# Buck_Converter.net
KiCad netlist of a schematic drawn in Altium Designer
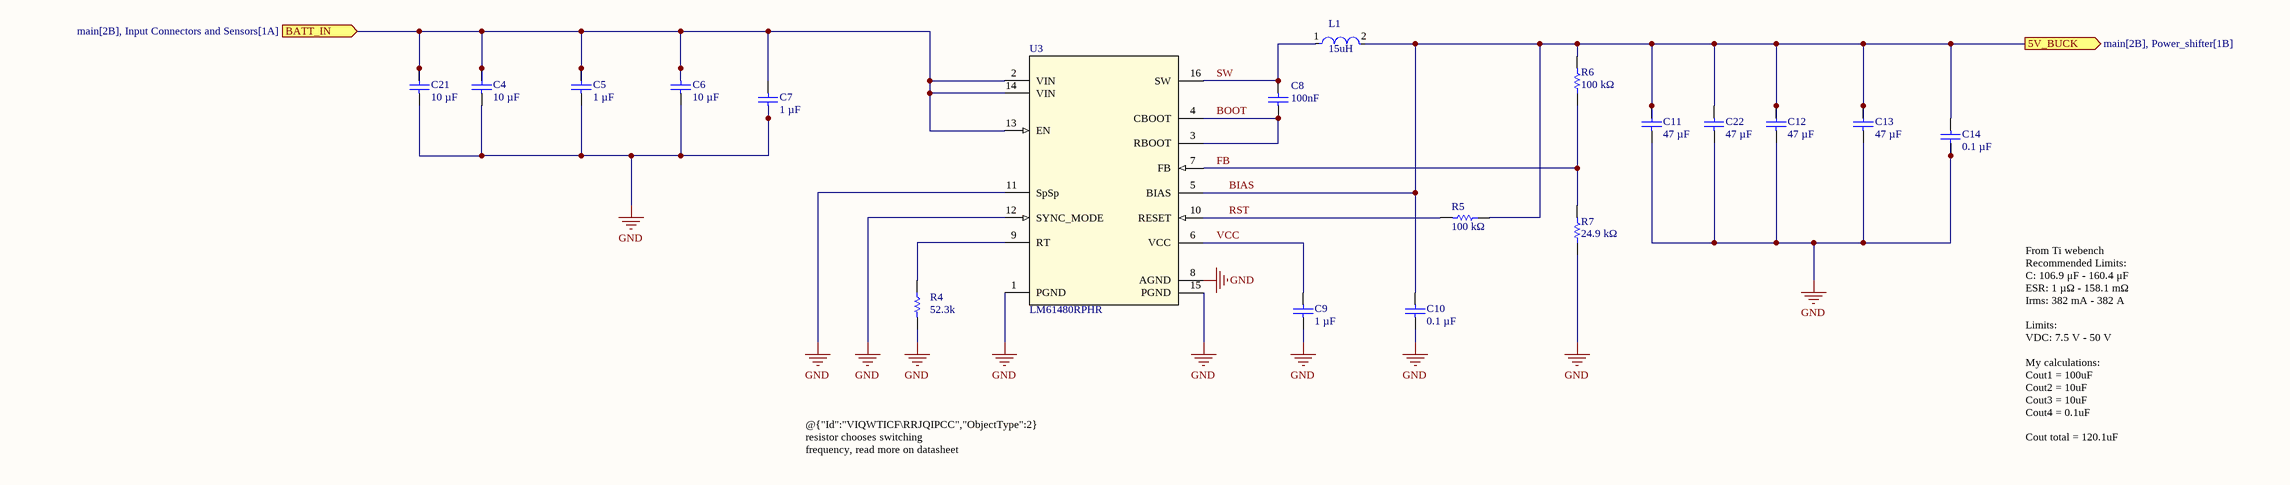
[diagram p0: Buck Converter.SchDoc]

(export (version "E")
  (design (tool "Eeschema 10.0.6"))
  (components
    (comp (ref "C4")
      (value "10 µF")
      (footprint "1210_CAPC3225L")
      (description "Capacitor (Semiconductor SIM Model)")
      (fields (field (name "PUBLISHER") "Altium Limited"))
      (libsource (lib "MiscDev 3") (part "Cap Semi"))
    )
    (comp (ref "C5")
      (value "1 µF")
      (footprint "0603_CAPC1608L")
      (description "Capacitor (Semiconductor SIM Model)")
      (fields (field (name "PUBLISHER") "Altium Limited"))
      (libsource (lib "MiscDev 3") (part "Cap Semi"))
    )
    (comp (ref "C6")
      (value "10 µF")
      (footprint "1210_CAPC3225L")
      (description "Capacitor (Semiconductor SIM Model)")
      (fields (field (name "PUBLISHER") "Altium Limited"))
      (libsource (lib "MiscDev 3") (part "Cap Semi"))
    )
    (comp (ref "C7")
      (value "1 µF")
      (footprint "0603_CAPC1608L")
      (description "Capacitor (Semiconductor SIM Model)")
      (fields (field (name "PUBLISHER") "Altium Limited"))
      (libsource (lib "MiscDev 3") (part "Cap Semi"))
    )
    (comp (ref "C8")
      (value "GRM155R71A104KA01D")
      (footprint "CAPC1005X55X25LL05T10")
      (description "Chip Capacitor, 0.1 uF, +/- 10%, 10 V, -55 to 125 degC, 0402 (1005 Metric), RoHS, Tape and Reel")
      (fields (field (name "CAPACITANCE") "100nF") (field (name "MANUFACTURER") "Murata"))
      (libsource (lib "Altium Content Vault") (part "CAP-NP-2"))
    )
    (comp (ref "C9")
      (value "1 µF")
      (footprint "0603_CAPC1608L")
      (description "Capacitor (Semiconductor SIM Model)")
      (fields (field (name "PUBLISHER") "Altium Limited"))
      (libsource (lib "MiscDev 3") (part "Cap Semi"))
    )
    (comp (ref "C10")
      (value "0.1 µF")
      (footprint "0402_CAPC1005L")
      (description "Capacitor (Semiconductor SIM Model)")
      (fields (field (name "PUBLISHER") "Altium Limited"))
      (libsource (lib "MiscDev 3") (part "Cap Semi"))
    )
    (comp (ref "C11")
      (value "47 µF")
      (footprint "1210_CAPC3225L")
      (description "Capacitor (Semiconductor SIM Model)")
      (fields (field (name "PUBLISHER") "Altium Limited"))
      (libsource (lib "MiscDev 3") (part "Cap Semi"))
    )
    (comp (ref "C12")
      (value "47 µF")
      (footprint "1210_CAPC3225L")
      (description "Capacitor (Semiconductor SIM Model)")
      (fields (field (name "PUBLISHER") "Altium Limited"))
      (libsource (lib "MiscDev 3") (part "Cap Semi"))
    )
    (comp (ref "C13")
      (value "47 µF")
      (footprint "1210_CAPC3225L")
      (description "Capacitor (Semiconductor SIM Model)")
      (fields (field (name "PUBLISHER") "Altium Limited"))
      (libsource (lib "MiscDev 3") (part "Cap Semi"))
    )
    (comp (ref "C14")
      (value "0.1 µF")
      (footprint "0402_CAPC1005L")
      (description "Capacitor (Semiconductor SIM Model)")
      (fields (field (name "PUBLISHER") "Altium Limited"))
      (libsource (lib "MiscDev 3") (part "Cap Semi"))
    )
    (comp (ref "C21")
      (value "10 µF")
      (footprint "1210_CAPC3225L")
      (description "Capacitor (Semiconductor SIM Model)")
      (fields (field (name "PUBLISHER") "Altium Limited"))
      (libsource (lib "MiscDev 3") (part "Cap Semi"))
    )
    (comp (ref "C22")
      (value "47 µF")
      (footprint "1210_CAPC3225L")
      (description "Capacitor (Semiconductor SIM Model)")
      (fields (field (name "PUBLISHER") "Altium Limited"))
      (libsource (lib "MiscDev 3") (part "Cap Semi"))
    )
    (comp (ref "L1")
      (value "SRR1260-150M")
      (footprint "FP-SRR1260-MFG")
      (description "FIXED IND 15UH 5A 27 MOHM SMD")
      (fields (field (name "INDUCTANCE") "15uH") (field (name "TOLERANCE") "20%"))
      (libsource (lib "Altium Content Vault") (part "725321dda6339637d4d059423bc1c3c"))
    )
    (comp (ref "R4")
      (value "CRCW040252K3FKED")
      (footprint "RESC1005X40X25LL05T05")
      (fields (field (name "MANUFACTURER") "Vishay Dale") (field (name "RESISTANCE") "52.3k"))
      (libsource (lib "Altium Content Vault") (part "RES"))
    )
    (comp (ref "R5")
      (value "100 kΩ")
      (footprint "0603_RESC1608L")
      (description "Semiconductor Resistor")
      (fields (field (name "Comment") "Res Semi") (field (name "PUBLISHER") "Altium Limited"))
      (libsource (lib "MiscDev 3") (part "Res Semi"))
    )
    (comp (ref "R6")
      (value "100 kΩ")
      (footprint "0603_RESC1608L")
      (description "Semiconductor Resistor")
      (fields (field (name "Comment") "Res Semi") (field (name "PUBLISHER") "Altium Limited"))
      (libsource (lib "MiscDev 3") (part "Res Semi"))
    )
    (comp (ref "R7")
      (value "24.9 kΩ")
      (footprint "0603_RESC1608L")
      (description "Semiconductor Resistor")
      (fields (field (name "Comment") "Res Semi") (field (name "PUBLISHER") "Altium Limited"))
      (libsource (lib "MiscDev 3") (part "Res Semi"))
    )
    (comp (ref "U3")
      (value "LM61480RPHR")
      (footprint "RPH0016A")
      (description "8-A buck converter optimized for power density and low EMI 16-VQFN-HR -40 to 150")
      (fields (field (name "COPYRIGHT") "Copyright (C) 2026 Ultra Librarian. All rights reserved."))
      (libsource (lib "LM61480RPHR") (part "LM61480RPHR"))
    )
  )
  (nets
    (net (code "1") (name "/BATT_IN") (class "Default")
      (node (ref "C21") (pin "1") (pinfunction "1_1") (pintype "passive"))
      (node (ref "C4") (pin "1") (pinfunction "1_1") (pintype "passive"))
      (node (ref "C5") (pin "1") (pinfunction "1_1") (pintype "passive"))
      (node (ref "C6") (pin "1") (pinfunction "1_1") (pintype "passive"))
      (node (ref "C7") (pin "1") (pinfunction "1_1") (pintype "passive"))
      (node (ref "U3") (pin "13") (pinfunction "EN_13") (pintype "input"))
      (node (ref "U3") (pin "14") (pinfunction "VIN_14") (pintype "power_in"))
      (node (ref "U3") (pin "2") (pinfunction "VIN_2") (pintype "power_in"))
    )
    (net (code "2") (name "/BIAS") (class "Default")
      (node (ref "C10") (pin "1") (pinfunction "1_1") (pintype "passive"))
      (node (ref "C11") (pin "1") (pinfunction "1_1") (pintype "passive"))
      (node (ref "C12") (pin "1") (pinfunction "1_1") (pintype "passive"))
      (node (ref "C13") (pin "1") (pinfunction "1_1") (pintype "passive"))
      (node (ref "C14") (pin "1") (pinfunction "1_1") (pintype "passive"))
      (node (ref "C22") (pin "1") (pinfunction "1_1") (pintype "passive"))
      (node (ref "L1") (pin "2") (pinfunction "2_2") (pintype "passive"))
      (node (ref "R5") (pin "1") (pinfunction "1_1") (pintype "passive"))
      (node (ref "R6") (pin "2") (pinfunction "2_2") (pintype "passive"))
      (node (ref "U3") (pin "5") (pinfunction "BIAS_5") (pintype "passive"))
    )
    (net (code "3") (name "/BOOT") (class "Default")
      (node (ref "C8") (pin "2") (pinfunction "2_2") (pintype "passive"))
      (node (ref "U3") (pin "3") (pinfunction "RBOOT_3") (pintype "passive"))
      (node (ref "U3") (pin "4") (pinfunction "CBOOT_4") (pintype "passive"))
    )
    (net (code "4") (name "/FB") (class "Default")
      (node (ref "R6") (pin "1") (pinfunction "1_1") (pintype "passive"))
      (node (ref "R7") (pin "2") (pinfunction "2_2") (pintype "passive"))
      (node (ref "U3") (pin "7") (pinfunction "FB_7") (pintype "input"))
    )
    (net (code "5") (name "/RST") (class "Default")
      (node (ref "R5") (pin "2") (pinfunction "2_2") (pintype "passive"))
      (node (ref "U3") (pin "10") (pinfunction "RESET_10") (pintype "input"))
    )
    (net (code "6") (name "/SW") (class "Default")
      (node (ref "C8") (pin "1") (pinfunction "1_1") (pintype "passive"))
      (node (ref "L1") (pin "1") (pinfunction "1_1") (pintype "passive"))
      (node (ref "U3") (pin "16") (pinfunction "SW_16") (pintype "power_in"))
    )
    (net (code "7") (name "/VCC") (class "Default")
      (node (ref "C9") (pin "1") (pinfunction "1_1") (pintype "passive"))
      (node (ref "U3") (pin "6") (pinfunction "VCC_6") (pintype "power_in"))
    )
    (net (code "8") (name "GND") (class "Default")
      (node (ref "C10") (pin "2") (pinfunction "2_2") (pintype "passive"))
      (node (ref "C11") (pin "2") (pinfunction "2_2") (pintype "passive"))
      (node (ref "C12") (pin "2") (pinfunction "2_2") (pintype "passive"))
      (node (ref "C13") (pin "2") (pinfunction "2_2") (pintype "passive"))
      (node (ref "C14") (pin "2") (pinfunction "2_2") (pintype "passive"))
      (node (ref "C21") (pin "2") (pinfunction "2_2") (pintype "passive"))
      (node (ref "C22") (pin "2") (pinfunction "2_2") (pintype "passive"))
      (node (ref "C4") (pin "2") (pinfunction "2_2") (pintype "passive"))
      (node (ref "C5") (pin "2") (pinfunction "2_2") (pintype "passive"))
      (node (ref "C6") (pin "2") (pinfunction "2_2") (pintype "passive"))
      (node (ref "C7") (pin "2") (pinfunction "2_2") (pintype "passive"))
      (node (ref "C9") (pin "2") (pinfunction "2_2") (pintype "passive"))
      (node (ref "R4") (pin "2") (pinfunction "2_2") (pintype "passive"))
      (node (ref "R7") (pin "1") (pinfunction "1_1") (pintype "passive"))
      (node (ref "U3") (pin "1") (pinfunction "PGND_1") (pintype "power_in"))
      (node (ref "U3") (pin "11") (pinfunction "SpSp_11") (pintype "passive"))
      (node (ref "U3") (pin "12") (pinfunction "SYNC_MODE_12") (pintype "input"))
      (node (ref "U3") (pin "15") (pinfunction "PGND_15") (pintype "power_in"))
      (node (ref "U3") (pin "8") (pinfunction "AGND_8") (pintype "power_in"))
    )
    (net (code "9") (name "Net-(U3-RT)") (class "Default")
      (node (ref "R4") (pin "1") (pinfunction "1_1") (pintype "passive"))
      (node (ref "U3") (pin "9") (pinfunction "RT_9") (pintype "passive"))
    )
  )
)
